# Lab11.net
KiCad netlist of a schematic drawn in Altium Designer
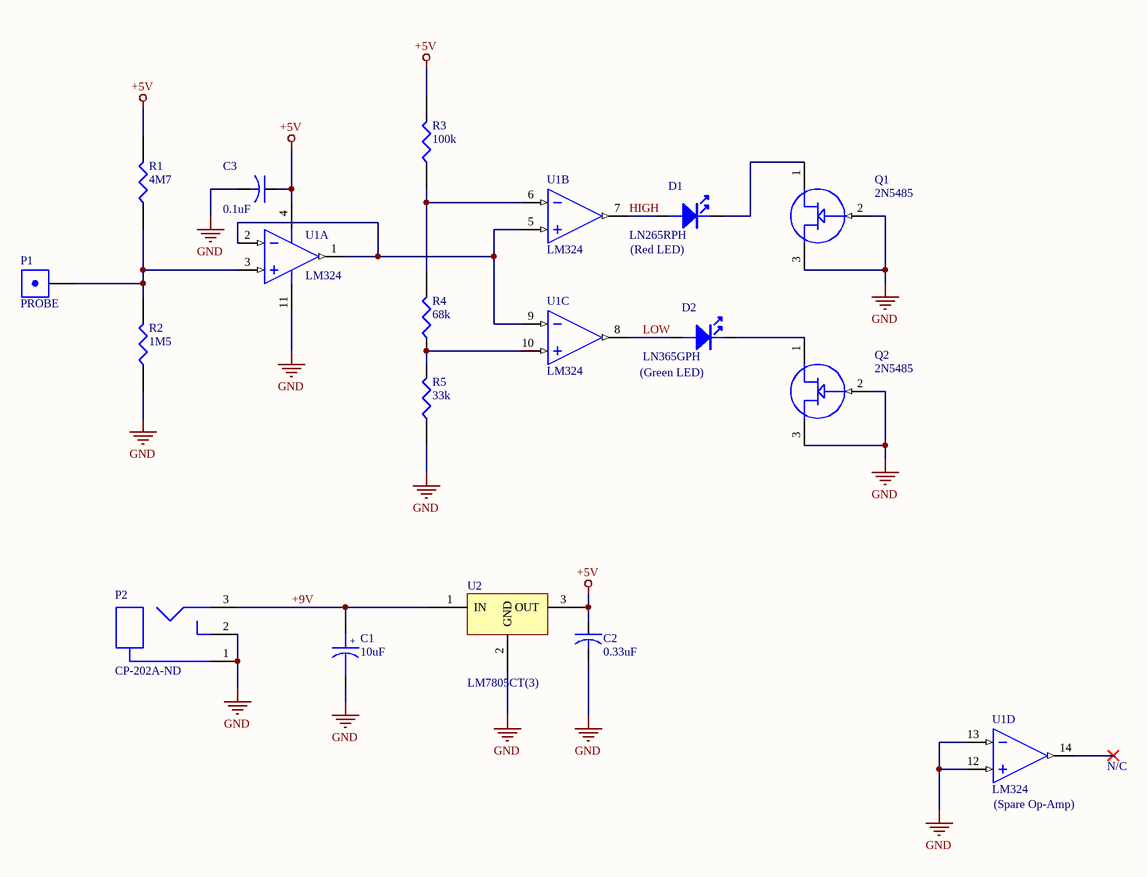
[diagram p0: Lab11.SchDoc]

(export (version "E")
  (design (tool "Eeschema 10.0.6"))
  (components
    (comp (ref "C1")
      (value "10uF")
      (footprint "RAD0.2-POL")
      (description "Polarized Electrolytic Capacitor")
      (libsource (lib "ECET231SCHLIB_Rev01") (part "CAPACITOR POL"))
    )
    (comp (ref "C2")
      (value "0.33uF")
      (footprint "RAD0.2")
      (description "Non-polarized Electrolytic Capacitor")
      (libsource (lib "ECET231SCHLIB_Rev01") (part "CAPACITOR"))
    )
    (comp (ref "C3")
      (value "0.1uF")
      (footprint "RAD0.2")
      (description "Non-polarized Electrolytic Capacitor")
      (libsource (lib "ECET231SCHLIB_Rev01") (part "CAPACITOR"))
    )
    (comp (ref "D1")
      (value "LN265RPH")
      (description "Light Emitting Diode LED")
      (libsource (lib "ECET231SCHLIB_Rev01") (part "LED"))
    )
    (comp (ref "D2")
      (value "LN365GPH")
      (description "Light Emitting Diode LED")
      (libsource (lib "ECET231SCHLIB_Rev01") (part "LED"))
    )
    (comp (ref "P1")
      (value "PROBE")
      (footprint "PROBE")
      (description "Probe")
      (libsource (lib "ECET231SCHLIB_Rev01") (part "PROBE"))
    )
    (comp (ref "P2")
      (value "CP-202A-ND")
      (description "Male Power Jack, PCB")
      (libsource (lib "ECET231SCHLIB_Rev01") (part "CP-202A-ND"))
    )
    (comp (ref "Q1")
      (value "2N5485")
      (footprint "TO-92A")
      (description "N-channel JFET")
      (libsource (lib "ECET231SCHLIB_Rev01") (part "2N5485"))
    )
    (comp (ref "Q2")
      (value "2N5485")
      (footprint "TO-92A")
      (description "N-channel JFET")
      (libsource (lib "ECET231SCHLIB_Rev01") (part "2N5485"))
    )
    (comp (ref "R1")
      (value "4M7")
      (footprint "axial0.5")
      (description "Resistor")
      (libsource (lib "ECET231SCHLIB_Rev01") (part "RES1"))
    )
    (comp (ref "R2")
      (value "1M5")
      (footprint "axial0.5")
      (description "Resistor")
      (libsource (lib "ECET231SCHLIB_Rev01") (part "RES1"))
    )
    (comp (ref "R3")
      (value "100k")
      (footprint "axial0.5")
      (description "Resistor")
      (libsource (lib "ECET231SCHLIB_Rev01") (part "RES1"))
    )
    (comp (ref "R4")
      (value "68k")
      (footprint "axial0.5")
      (description "Resistor")
      (libsource (lib "ECET231SCHLIB_Rev01") (part "RES1"))
    )
    (comp (ref "R5")
      (value "33k")
      (footprint "axial0.5")
      (description "Resistor")
      (libsource (lib "ECET231SCHLIB_Rev01") (part "RES1"))
    )
    (comp (ref "U1")
      (value "LM324")
      (footprint "DIP14")
      (description "Quad Operational Amplifier")
      (libsource (lib "ECET231SCHLIB_Rev01") (part "LM324"))
    )
    (comp (ref "U2")
      (value "LM7805CT(3)")
      (description "Three Terminal Voltage Regulator")
      (libsource (lib "ECET231SCHLIB_Rev01") (part "LM7805CT(3)"))
    )
  )
  (nets
    (net (code "1") (name "+5V") (class "Default")
      (node (ref "C2") (pin "1") (pinfunction "1_1") (pintype "passive"))
      (node (ref "C3") (pin "1") (pinfunction "1_1") (pintype "passive"))
      (node (ref "R1") (pin "2") (pinfunction "2_2") (pintype "passive"))
      (node (ref "R3") (pin "2") (pinfunction "2_2") (pintype "passive"))
      (node (ref "U1") (pin "4") (pinfunction "VCC_4") (pintype "power_in"))
      (node (ref "U2") (pin "3") (pinfunction "OUT_3") (pintype "power_in"))
    )
    (net (code "2") (name "/+9V") (class "Default")
      (node (ref "C1") (pin "1") (pinfunction "1_1") (pintype "passive"))
      (node (ref "P2") (pin "3") (pinfunction "3_3") (pintype "passive"))
      (node (ref "U2") (pin "1") (pinfunction "IN_1") (pintype "power_in"))
    )
    (net (code "3") (name "/HIGH") (class "Default")
      (node (ref "D1") (pin "A") (pinfunction "A_A") (pintype "passive"))
      (node (ref "U1") (pin "7") (pinfunction "2_OUT_7") (pintype "output"))
    )
    (net (code "4") (name "/LOW") (class "Default")
      (node (ref "D2") (pin "A") (pinfunction "A_A") (pintype "passive"))
      (node (ref "U1") (pin "8") (pinfunction "3_OUT_8") (pintype "output"))
    )
    (net (code "5") (name "GND") (class "Default")
      (node (ref "C1") (pin "2") (pinfunction "2_2") (pintype "passive"))
      (node (ref "C2") (pin "2") (pinfunction "2_2") (pintype "passive"))
      (node (ref "C3") (pin "2") (pinfunction "2_2") (pintype "passive"))
      (node (ref "P2") (pin "1") (pinfunction "1_1") (pintype "passive"))
      (node (ref "P2") (pin "2") (pinfunction "2_2") (pintype "passive"))
      (node (ref "Q1") (pin "2") (pinfunction "2_2") (pintype "input"))
      (node (ref "Q1") (pin "3") (pinfunction "3_3") (pintype "passive"))
      (node (ref "Q2") (pin "2") (pinfunction "2_2") (pintype "input"))
      (node (ref "Q2") (pin "3") (pinfunction "3_3") (pintype "passive"))
      (node (ref "R2") (pin "1") (pinfunction "1_1") (pintype "passive"))
      (node (ref "R5") (pin "1") (pinfunction "1_1") (pintype "passive"))
      (node (ref "U1") (pin "11") (pinfunction "VEE_11") (pintype "power_in"))
      (node (ref "U1") (pin "12") (pinfunction "4_IN+_12") (pintype "input"))
      (node (ref "U1") (pin "13") (pinfunction "4_IN-_13") (pintype "input"))
      (node (ref "U2") (pin "2") (pinfunction "GND_2") (pintype "power_in"))
    )
    (net (code "6") (name "Net-(D1-PadK)") (class "Default")
      (node (ref "D1") (pin "K") (pinfunction "K_K") (pintype "passive"))
      (node (ref "Q1") (pin "1") (pinfunction "1_1") (pintype "passive"))
    )
    (net (code "7") (name "Net-(D2-PadK)") (class "Default")
      (node (ref "D2") (pin "K") (pinfunction "K_K") (pintype "passive"))
      (node (ref "Q2") (pin "1") (pinfunction "1_1") (pintype "passive"))
    )
    (net (code "8") (name "Net-(U1A-1_IN+)") (class "Default")
      (node (ref "P1") (pin "1") (pinfunction "1_1") (pintype "passive"))
      (node (ref "R1") (pin "1") (pinfunction "1_1") (pintype "passive"))
      (node (ref "R2") (pin "2") (pinfunction "2_2") (pintype "passive"))
      (node (ref "U1") (pin "3") (pinfunction "1_IN+_3") (pintype "input"))
    )
    (net (code "9") (name "Net-(U1A-1_IN-)") (class "Default")
      (node (ref "U1") (pin "1") (pinfunction "1_OUT_1") (pintype "output"))
      (node (ref "U1") (pin "2") (pinfunction "1_IN-_2") (pintype "input"))
      (node (ref "U1") (pin "5") (pinfunction "2_IN+_5") (pintype "input"))
      (node (ref "U1") (pin "9") (pinfunction "3_IN-_9") (pintype "input"))
    )
    (net (code "10") (name "Net-(U1B-2_IN-)") (class "Default")
      (node (ref "R3") (pin "1") (pinfunction "1_1") (pintype "passive"))
      (node (ref "R4") (pin "2") (pinfunction "2_2") (pintype "passive"))
      (node (ref "U1") (pin "6") (pinfunction "2_IN-_6") (pintype "input"))
    )
    (net (code "11") (name "Net-(U1C-3_IN+)") (class "Default")
      (node (ref "R4") (pin "1") (pinfunction "1_1") (pintype "passive"))
      (node (ref "R5") (pin "2") (pinfunction "2_2") (pintype "passive"))
      (node (ref "U1") (pin "10") (pinfunction "3_IN+_10") (pintype "input"))
    )
    (net (code "12") (name "unconnected-(U1D-4_OUT-Pad14)") (class "Default")
      (node (ref "U1") (pin "14") (pinfunction "4_OUT_14") (pintype "output"))
    )
  )
)
